# shiftregister.net
KiCad netlist of a schematic drawn in EAGLE
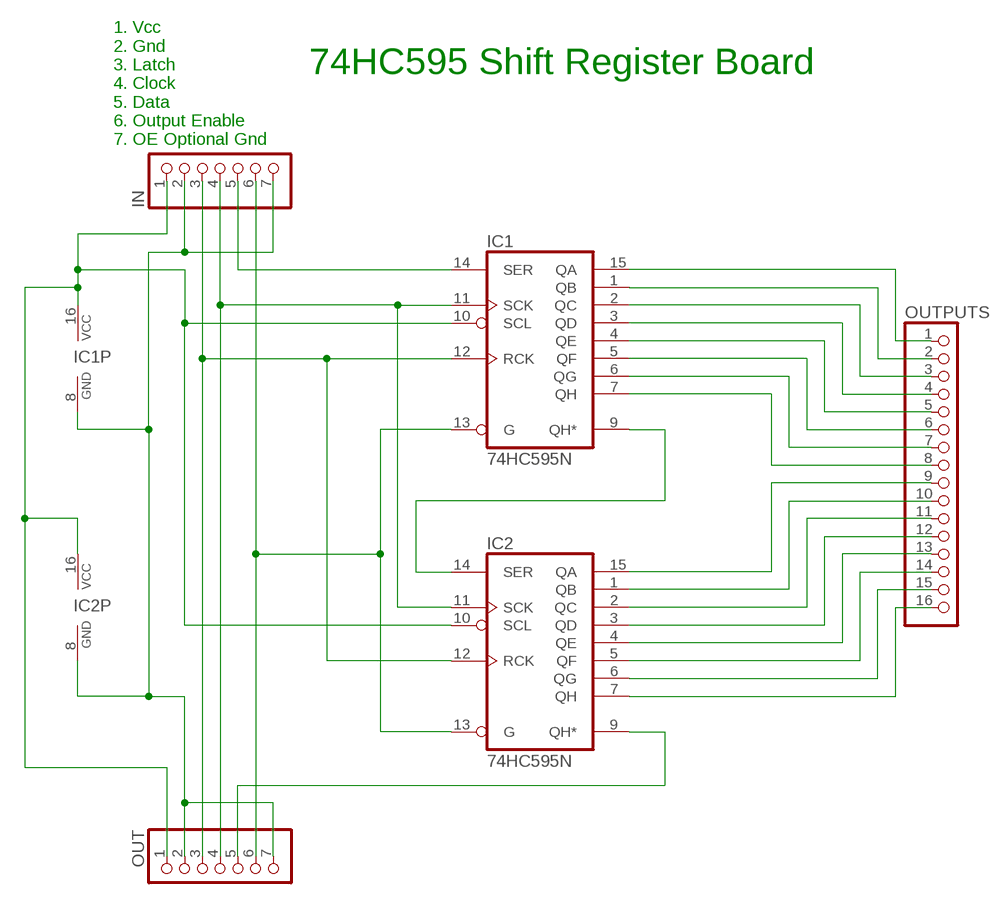
[diagram p0: schematic, sheet 1]

(export (version "E")
  (design (tool "Eeschema 10.0.6"))
  (components
    (comp (ref "IC1")
      (value "74HC595N")
      (footprint "eagle-import:DIL16")
      (libsource (lib "eagle-import") (part "74595NHC"))
    )
    (comp (ref "IC2")
      (value "74HC595N")
      (footprint "eagle-import:DIL16")
      (libsource (lib "eagle-import") (part "74595NHC"))
    )
    (comp (ref "IN")
      (value "PINHD-1X7")
      (footprint "eagle-import:1X07")
      (libsource (lib "eagle-import") (part "PINHD-1X7"))
    )
    (comp (ref "OUT")
      (value "PINHD-1X7")
      (footprint "eagle-import:1X07")
      (libsource (lib "eagle-import") (part "PINHD-1X7"))
    )
    (comp (ref "OUTPUTS")
      (value "PINHD-1X16")
      (footprint "eagle-import:1X16")
      (libsource (lib "eagle-import") (part "PINHD-1X16"))
    )
  )
  (nets
    (net (code "1") (name "Net-(IC1A-G)") (class "Default")
      (node (ref "IC1") (pin "13") (pinfunction "G_13") (pintype "input"))
      (node (ref "IC2") (pin "13") (pinfunction "G_13") (pintype "input"))
      (node (ref "IN") (pin "6") (pinfunction "6_6") (pintype "passive"))
      (node (ref "OUT") (pin "6") (pinfunction "6_6") (pintype "passive"))
    )
    (net (code "2") (name "Net-(IC1A-QA)") (class "Default")
      (node (ref "IC1") (pin "15") (pinfunction "QA_15") (pintype "tri_state"))
      (node (ref "OUTPUTS") (pin "1") (pinfunction "1_1") (pintype "passive"))
    )
    (net (code "3") (name "Net-(IC1A-QB)") (class "Default")
      (node (ref "IC1") (pin "1") (pinfunction "QB_1") (pintype "tri_state"))
      (node (ref "OUTPUTS") (pin "2") (pinfunction "2_2") (pintype "passive"))
    )
    (net (code "4") (name "Net-(IC1A-QC)") (class "Default")
      (node (ref "IC1") (pin "2") (pinfunction "QC_2") (pintype "tri_state"))
      (node (ref "OUTPUTS") (pin "3") (pinfunction "3_3") (pintype "passive"))
    )
    (net (code "5") (name "Net-(IC1A-QD)") (class "Default")
      (node (ref "IC1") (pin "3") (pinfunction "QD_3") (pintype "tri_state"))
      (node (ref "OUTPUTS") (pin "4") (pinfunction "4_4") (pintype "passive"))
    )
    (net (code "6") (name "Net-(IC1A-QE)") (class "Default")
      (node (ref "IC1") (pin "4") (pinfunction "QE_4") (pintype "tri_state"))
      (node (ref "OUTPUTS") (pin "5") (pinfunction "5_5") (pintype "passive"))
    )
    (net (code "7") (name "Net-(IC1A-QF)") (class "Default")
      (node (ref "IC1") (pin "5") (pinfunction "QF_5") (pintype "tri_state"))
      (node (ref "OUTPUTS") (pin "6") (pinfunction "6_6") (pintype "passive"))
    )
    (net (code "8") (name "Net-(IC1A-QG)") (class "Default")
      (node (ref "IC1") (pin "6") (pinfunction "QG_6") (pintype "tri_state"))
      (node (ref "OUTPUTS") (pin "7") (pinfunction "7_7") (pintype "passive"))
    )
    (net (code "9") (name "Net-(IC1A-QH)") (class "Default")
      (node (ref "IC1") (pin "7") (pinfunction "QH_7") (pintype "tri_state"))
      (node (ref "OUTPUTS") (pin "8") (pinfunction "8_8") (pintype "passive"))
    )
    (net (code "10") (name "Net-(IC1A-QH*)") (class "Default")
      (node (ref "IC1") (pin "9") (pinfunction "QH*_9") (pintype "tri_state"))
      (node (ref "IC2") (pin "14") (pinfunction "SER_14") (pintype "input"))
    )
    (net (code "11") (name "Net-(IC1A-RCK)") (class "Default")
      (node (ref "IC1") (pin "12") (pinfunction "RCK_12") (pintype "input"))
      (node (ref "IC2") (pin "12") (pinfunction "RCK_12") (pintype "input"))
      (node (ref "IN") (pin "3") (pinfunction "3_3") (pintype "passive"))
      (node (ref "OUT") (pin "3") (pinfunction "3_3") (pintype "passive"))
    )
    (net (code "12") (name "Net-(IC1A-SCK)") (class "Default")
      (node (ref "IC1") (pin "11") (pinfunction "SCK_11") (pintype "input"))
      (node (ref "IC2") (pin "11") (pinfunction "SCK_11") (pintype "input"))
      (node (ref "IN") (pin "4") (pinfunction "4_4") (pintype "passive"))
      (node (ref "OUT") (pin "4") (pinfunction "4_4") (pintype "passive"))
    )
    (net (code "13") (name "Net-(IC1A-SCL)") (class "Default")
      (node (ref "IC1") (pin "10") (pinfunction "SCL_10") (pintype "input"))
      (node (ref "IC1") (pin "16") (pinfunction "VCC_16") (pintype "power_in"))
      (node (ref "IC2") (pin "10") (pinfunction "SCL_10") (pintype "input"))
      (node (ref "IC2") (pin "16") (pinfunction "VCC_16") (pintype "power_in"))
      (node (ref "IN") (pin "1") (pinfunction "1_1") (pintype "passive"))
      (node (ref "OUT") (pin "1") (pinfunction "1_1") (pintype "passive"))
    )
    (net (code "14") (name "Net-(IC1A-SER)") (class "Default")
      (node (ref "IC1") (pin "14") (pinfunction "SER_14") (pintype "input"))
      (node (ref "IN") (pin "5") (pinfunction "5_5") (pintype "passive"))
    )
    (net (code "15") (name "Net-(IC1B-GND)") (class "Default")
      (node (ref "IC1") (pin "8") (pinfunction "GND_8") (pintype "power_in"))
      (node (ref "IC2") (pin "8") (pinfunction "GND_8") (pintype "power_in"))
      (node (ref "IN") (pin "2") (pinfunction "2_2") (pintype "passive"))
      (node (ref "IN") (pin "7") (pinfunction "7_7") (pintype "passive"))
      (node (ref "OUT") (pin "2") (pinfunction "2_2") (pintype "passive"))
      (node (ref "OUT") (pin "7") (pinfunction "7_7") (pintype "passive"))
    )
    (net (code "16") (name "Net-(IC2A-QA)") (class "Default")
      (node (ref "IC2") (pin "15") (pinfunction "QA_15") (pintype "tri_state"))
      (node (ref "OUTPUTS") (pin "9") (pinfunction "9_9") (pintype "passive"))
    )
    (net (code "17") (name "Net-(IC2A-QB)") (class "Default")
      (node (ref "IC2") (pin "1") (pinfunction "QB_1") (pintype "tri_state"))
      (node (ref "OUTPUTS") (pin "10") (pinfunction "10_10") (pintype "passive"))
    )
    (net (code "18") (name "Net-(IC2A-QC)") (class "Default")
      (node (ref "IC2") (pin "2") (pinfunction "QC_2") (pintype "tri_state"))
      (node (ref "OUTPUTS") (pin "11") (pinfunction "11_11") (pintype "passive"))
    )
    (net (code "19") (name "Net-(IC2A-QD)") (class "Default")
      (node (ref "IC2") (pin "3") (pinfunction "QD_3") (pintype "tri_state"))
      (node (ref "OUTPUTS") (pin "12") (pinfunction "12_12") (pintype "passive"))
    )
    (net (code "20") (name "Net-(IC2A-QE)") (class "Default")
      (node (ref "IC2") (pin "4") (pinfunction "QE_4") (pintype "tri_state"))
      (node (ref "OUTPUTS") (pin "13") (pinfunction "13_13") (pintype "passive"))
    )
    (net (code "21") (name "Net-(IC2A-QF)") (class "Default")
      (node (ref "IC2") (pin "5") (pinfunction "QF_5") (pintype "tri_state"))
      (node (ref "OUTPUTS") (pin "14") (pinfunction "14_14") (pintype "passive"))
    )
    (net (code "22") (name "Net-(IC2A-QG)") (class "Default")
      (node (ref "IC2") (pin "6") (pinfunction "QG_6") (pintype "tri_state"))
      (node (ref "OUTPUTS") (pin "15") (pinfunction "15_15") (pintype "passive"))
    )
    (net (code "23") (name "Net-(IC2A-QH)") (class "Default")
      (node (ref "IC2") (pin "7") (pinfunction "QH_7") (pintype "tri_state"))
      (node (ref "OUTPUTS") (pin "16") (pinfunction "16_16") (pintype "passive"))
    )
    (net (code "24") (name "Net-(IC2A-QH*)") (class "Default")
      (node (ref "IC2") (pin "9") (pinfunction "QH*_9") (pintype "tri_state"))
      (node (ref "OUT") (pin "5") (pinfunction "5_5") (pintype "passive"))
    )
  )
)
